# PulverTech_v1.net
KiCad netlist of a schematic drawn in EAGLE
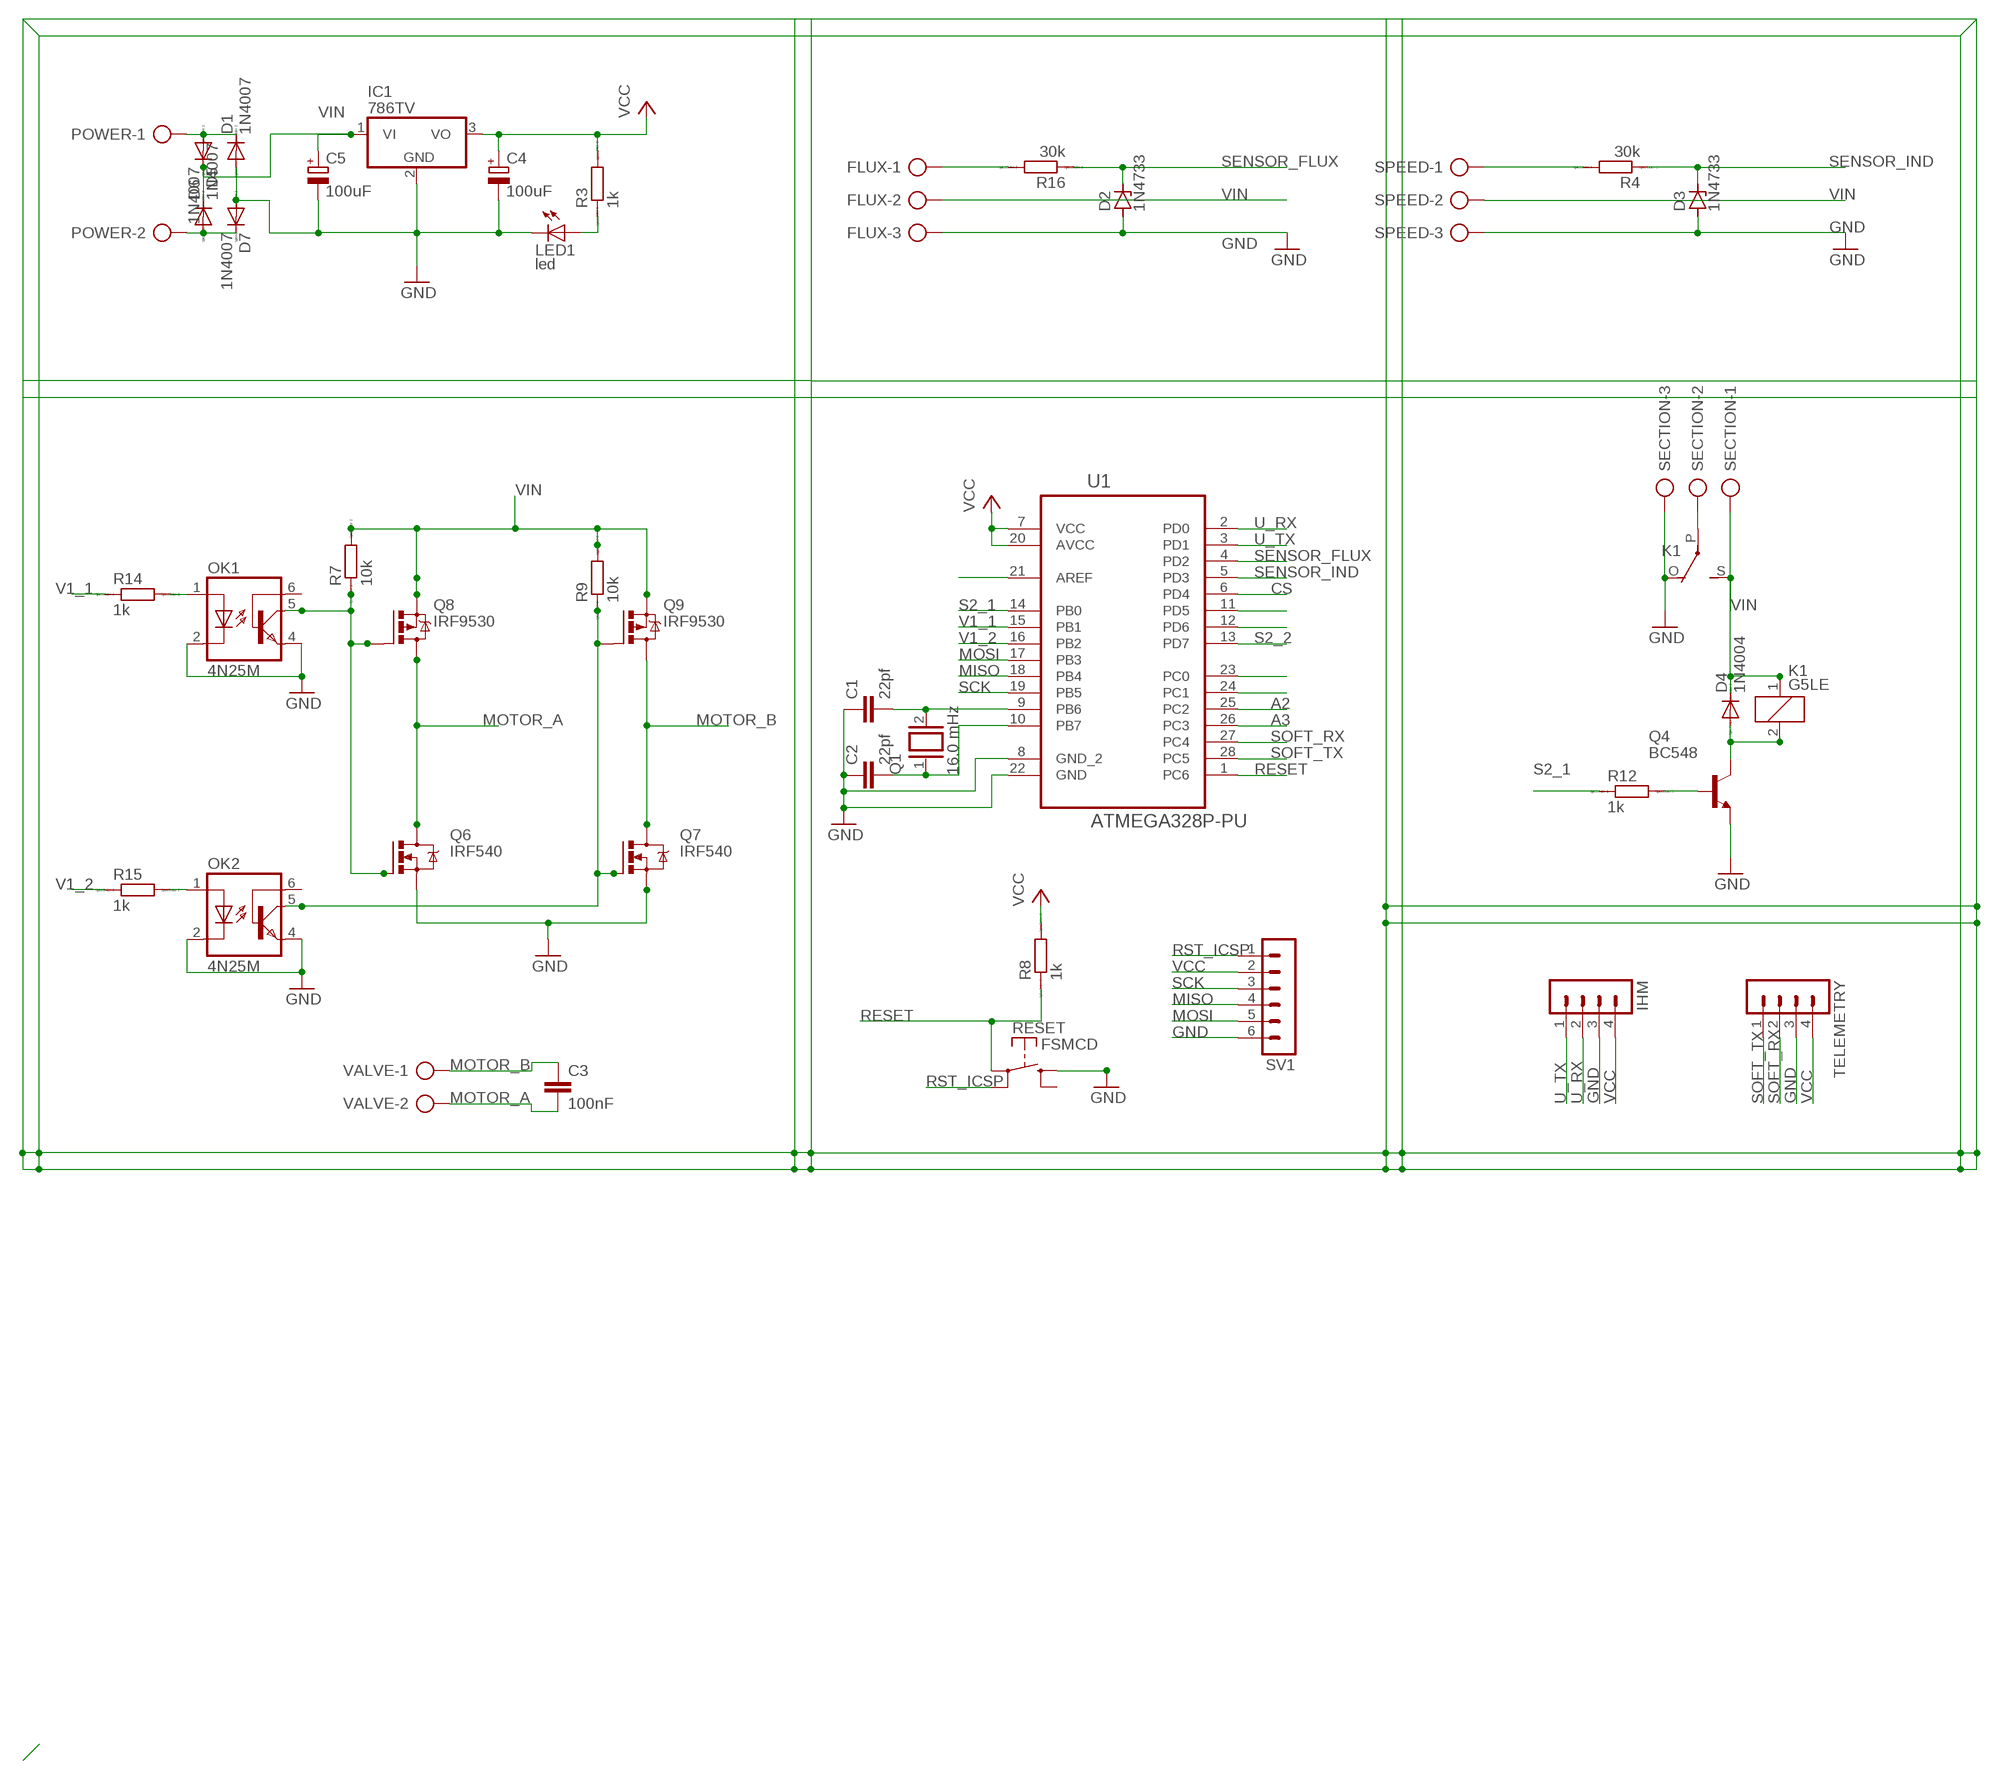
[diagram p0: schematic, sheet 1]

(export (version "E")
  (design (tool "Eeschema 10.0.6"))
  (components
    (comp (ref "C1")
      (value "22pf")
      (footprint "eagle-import:C025-025X050")
      (libsource (lib "eagle-import") (part "C-EU025-025X050"))
    )
    (comp (ref "C2")
      (value "22pf")
      (footprint "eagle-import:C025-025X050")
      (libsource (lib "eagle-import") (part "C-EU025-025X050"))
    )
    (comp (ref "C3")
      (value "100nF")
      (footprint "eagle-import:C2.5-2")
      (libsource (lib "eagle-import") (part "C2.5/2"))
    )
    (comp (ref "C4")
      (value "100uF")
      (footprint "eagle-import:E2,5-5")
      (libsource (lib "eagle-import") (part "CPOL-EUE2.5-5"))
    )
    (comp (ref "C5")
      (value "100uF")
      (footprint "eagle-import:E2,5-5")
      (libsource (lib "eagle-import") (part "CPOL-EUE2.5-5"))
    )
    (comp (ref "D1")
      (value "1N4007")
      (footprint "eagle-import:DO41-10")
      (libsource (lib "eagle-import") (part "1N4004"))
    )
    (comp (ref "D2")
      (value "1N4733")
      (footprint "eagle-import:DO41Z10")
      (libsource (lib "eagle-import") (part "1N4728"))
    )
    (comp (ref "D3")
      (value "1N4733")
      (footprint "eagle-import:DO41Z10")
      (libsource (lib "eagle-import") (part "1N4728"))
    )
    (comp (ref "D4")
      (value "1N4004")
      (footprint "eagle-import:DO41-10")
      (libsource (lib "eagle-import") (part "1N4004"))
    )
    (comp (ref "D5")
      (value "1N4007")
      (footprint "eagle-import:DO41-10")
      (libsource (lib "eagle-import") (part "1N4004"))
    )
    (comp (ref "D6")
      (value "1N4007")
      (footprint "eagle-import:DO41-10")
      (libsource (lib "eagle-import") (part "1N4004"))
    )
    (comp (ref "D7")
      (value "1N4007")
      (footprint "eagle-import:DO41-10")
      (libsource (lib "eagle-import") (part "1N4004"))
    )
    (comp (ref "FLUX")
      (value "AK500/3")
      (footprint "eagle-import:AK500_3")
      (libsource (lib "eagle-import") (part "AK500/3"))
    )
    (comp (ref "IC1")
      (value "786TV")
      (footprint "eagle-import:TO220V")
      (libsource (lib "eagle-import") (part "78TV6"))
    )
    (comp (ref "IHM")
      (value "MA04-1")
      (footprint "eagle-import:MA04-1")
      (libsource (lib "eagle-import") (part "MA04-1"))
    )
    (comp (ref "K1")
      (value "G5LE")
      (footprint "eagle-import:G5LE")
      (libsource (lib "eagle-import") (part "G5LE"))
    )
    (comp (ref "LED1")
      (value "led")
      (footprint "eagle-import:LED3MM")
      (libsource (lib "eagle-import") (part "LED3MM"))
    )
    (comp (ref "OK1")
      (value "4N25M")
      (footprint "eagle-import:DIL06")
      (fields (field (name "MPN") "4N25-M"))
      (libsource (lib "eagle-import") (part "4N?M25"))
    )
    (comp (ref "OK2")
      (value "4N25M")
      (footprint "eagle-import:DIL06")
      (fields (field (name "MPN") "4N25-M"))
      (libsource (lib "eagle-import") (part "4N?M25"))
    )
    (comp (ref "POWER")
      (value "AK500/2")
      (footprint "eagle-import:AK500_2")
      (libsource (lib "eagle-import") (part "AK500/2"))
    )
    (comp (ref "Q1")
      (value "16.0 mHz")
      (footprint "eagle-import:QS")
      (libsource (lib "eagle-import") (part "XTAL/S"))
    )
    (comp (ref "Q4")
      (value "BC548")
      (footprint "eagle-import:TO92-EBC")
      (libsource (lib "eagle-import") (part "BC548"))
    )
    (comp (ref "Q6")
      (value "IRF540")
      (footprint "eagle-import:TO220BV")
      (libsource (lib "eagle-import") (part "IRF540"))
    )
    (comp (ref "Q7")
      (value "IRF540")
      (footprint "eagle-import:TO220BV")
      (libsource (lib "eagle-import") (part "IRF540"))
    )
    (comp (ref "Q8")
      (value "IRF9530")
      (footprint "eagle-import:TO220BV")
      (libsource (lib "eagle-import") (part "IRF9530"))
    )
    (comp (ref "Q9")
      (value "IRF9530")
      (footprint "eagle-import:TO220BV")
      (libsource (lib "eagle-import") (part "IRF9530"))
    )
    (comp (ref "R3")
      (value "1k")
      (footprint "eagle-import:0204_7")
      (libsource (lib "eagle-import") (part "R0204/7"))
    )
    (comp (ref "R4")
      (value "30k")
      (footprint "eagle-import:0204_7")
      (libsource (lib "eagle-import") (part "R0204/7"))
    )
    (comp (ref "R7")
      (value "10k")
      (footprint "eagle-import:0204_7")
      (libsource (lib "eagle-import") (part "R0204/7"))
    )
    (comp (ref "R8")
      (value "1k")
      (footprint "eagle-import:0204_7")
      (libsource (lib "eagle-import") (part "R0204/7"))
    )
    (comp (ref "R9")
      (value "10k")
      (footprint "eagle-import:0204_7")
      (libsource (lib "eagle-import") (part "R0204/7"))
    )
    (comp (ref "R12")
      (value "1k")
      (footprint "eagle-import:0204_7")
      (libsource (lib "eagle-import") (part "R0204/7"))
    )
    (comp (ref "R14")
      (value "1k")
      (footprint "eagle-import:0204_7")
      (libsource (lib "eagle-import") (part "R0204/7"))
    )
    (comp (ref "R15")
      (value "1k")
      (footprint "eagle-import:0204_7")
      (libsource (lib "eagle-import") (part "R0204/7"))
    )
    (comp (ref "R16")
      (value "30k")
      (footprint "eagle-import:0204_7")
      (libsource (lib "eagle-import") (part "R0204/7"))
    )
    (comp (ref "RESET")
      (value "FSMCD")
      (footprint "eagle-import:FSMCD")
      (libsource (lib "eagle-import") (part "FSMCD"))
    )
    (comp (ref "SECTION")
      (value "AK500/3")
      (footprint "eagle-import:AK500_3")
      (libsource (lib "eagle-import") (part "AK500/3"))
    )
    (comp (ref "SPEED")
      (value "AK500/3")
      (footprint "eagle-import:AK500_3")
      (libsource (lib "eagle-import") (part "AK500/3"))
    )
    (comp (ref "SV1")
      (value "MA06-1")
      (footprint "eagle-import:MA06-1")
      (libsource (lib "eagle-import") (part "MA06-1"))
    )
    (comp (ref "TELEMETRY")
      (value "MA04-1")
      (footprint "eagle-import:MA04-1")
      (libsource (lib "eagle-import") (part "MA04-1"))
    )
    (comp (ref "U1")
      (value "ATMEGA328P-PU")
      (footprint "eagle-import:DIP254P762X457-28")
      (libsource (lib "eagle-import") (part "ATMEGA328P-PU"))
    )
    (comp (ref "VALVE")
      (value "AK500/2")
      (footprint "eagle-import:AK500_2")
      (libsource (lib "eagle-import") (part "AK500/2"))
    )
  )
  (nets
    (net (code "1") (name "/A2") (class "Default")
      (node (ref "U1") (pin "25") (pinfunction "PC2_25") (pintype "bidirectional"))
    )
    (net (code "2") (name "/A3") (class "Default")
      (node (ref "U1") (pin "26") (pinfunction "PC3_26") (pintype "bidirectional"))
    )
    (net (code "3") (name "/CS") (class "Default")
      (node (ref "U1") (pin "6") (pinfunction "PD4_6") (pintype "bidirectional"))
    )
    (net (code "4") (name "/MISO") (class "Default")
      (node (ref "SV1") (pin "4") (pinfunction "4_4") (pintype "passive"))
      (node (ref "U1") (pin "18") (pinfunction "PB4_18") (pintype "bidirectional"))
    )
    (net (code "5") (name "/MOSI") (class "Default")
      (node (ref "SV1") (pin "5") (pinfunction "5_5") (pintype "passive"))
      (node (ref "U1") (pin "17") (pinfunction "PB3_17") (pintype "bidirectional"))
    )
    (net (code "6") (name "/MOTOR_A") (class "Default")
      (node (ref "C3") (pin "2") (pinfunction "2_2") (pintype "passive"))
      (node (ref "Q6") (pin "D") (pinfunction "D_D") (pintype "passive"))
      (node (ref "Q8") (pin "D") (pinfunction "D_D") (pintype "passive"))
      (node (ref "VALVE") (pin "2") (pinfunction "KL_2") (pintype "passive"))
    )
    (net (code "7") (name "/MOTOR_B") (class "Default")
      (node (ref "C3") (pin "1") (pinfunction "1_1") (pintype "passive"))
      (node (ref "Q7") (pin "D") (pinfunction "D_D") (pintype "passive"))
      (node (ref "Q9") (pin "D") (pinfunction "D_D") (pintype "passive"))
      (node (ref "VALVE") (pin "1") (pinfunction "KL_1") (pintype "passive"))
    )
    (net (code "8") (name "/RESET") (class "Default")
      (node (ref "R8") (pin "1") (pinfunction "1_1") (pintype "passive"))
      (node (ref "RESET") (pin "P$1") (pinfunction "P_P$1") (pintype "passive"))
      (node (ref "U1") (pin "1") (pinfunction "PC6_1") (pintype "bidirectional"))
    )
    (net (code "9") (name "/RST_ICSP") (class "Default")
      (node (ref "RESET") (pin "P$2") (pinfunction "P_P$2") (pintype "passive"))
      (node (ref "SV1") (pin "1") (pinfunction "1_1") (pintype "passive"))
    )
    (net (code "10") (name "/S2_1") (class "Default")
      (node (ref "R12") (pin "1") (pinfunction "1_1") (pintype "passive"))
      (node (ref "U1") (pin "14") (pinfunction "PB0_14") (pintype "bidirectional"))
    )
    (net (code "11") (name "/S2_2") (class "Default")
      (node (ref "U1") (pin "13") (pinfunction "PD7_13") (pintype "bidirectional"))
    )
    (net (code "12") (name "/SCK") (class "Default")
      (node (ref "SV1") (pin "3") (pinfunction "3_3") (pintype "passive"))
      (node (ref "U1") (pin "19") (pinfunction "PB5_19") (pintype "bidirectional"))
    )
    (net (code "13") (name "/SENSOR_FLUX") (class "Default")
      (node (ref "D2") (pin "C") (pinfunction "C_C") (pintype "passive"))
      (node (ref "R16") (pin "1") (pinfunction "1_1") (pintype "passive"))
      (node (ref "U1") (pin "4") (pinfunction "PD2_4") (pintype "bidirectional"))
    )
    (net (code "14") (name "/SENSOR_IND") (class "Default")
      (node (ref "D3") (pin "C") (pinfunction "C_C") (pintype "passive"))
      (node (ref "R4") (pin "1") (pinfunction "1_1") (pintype "passive"))
      (node (ref "U1") (pin "5") (pinfunction "PD3_5") (pintype "bidirectional"))
    )
    (net (code "15") (name "/SOFT_RX") (class "Default")
      (node (ref "TELEMETRY") (pin "2") (pinfunction "2_2") (pintype "passive"))
      (node (ref "U1") (pin "27") (pinfunction "PC4_27") (pintype "bidirectional"))
    )
    (net (code "16") (name "/SOFT_TX") (class "Default")
      (node (ref "TELEMETRY") (pin "1") (pinfunction "1_1") (pintype "passive"))
      (node (ref "U1") (pin "28") (pinfunction "PC5_28") (pintype "bidirectional"))
    )
    (net (code "17") (name "/U_RX") (class "Default")
      (node (ref "IHM") (pin "2") (pinfunction "2_2") (pintype "passive"))
      (node (ref "U1") (pin "2") (pinfunction "PD0_2") (pintype "bidirectional"))
    )
    (net (code "18") (name "/U_TX") (class "Default")
      (node (ref "IHM") (pin "1") (pinfunction "1_1") (pintype "passive"))
      (node (ref "U1") (pin "3") (pinfunction "PD1_3") (pintype "bidirectional"))
    )
    (net (code "19") (name "/V1_1") (class "Default")
      (node (ref "R14") (pin "1") (pinfunction "1_1") (pintype "passive"))
      (node (ref "U1") (pin "15") (pinfunction "PB1_15") (pintype "bidirectional"))
    )
    (net (code "20") (name "/V1_2") (class "Default")
      (node (ref "R15") (pin "1") (pinfunction "1_1") (pintype "passive"))
      (node (ref "U1") (pin "16") (pinfunction "PB2_16") (pintype "bidirectional"))
    )
    (net (code "21") (name "/VIN") (class "Default")
      (node (ref "C5") (pin "+") (pinfunction "+_+") (pintype "passive"))
      (node (ref "D4") (pin "C") (pinfunction "C_C") (pintype "passive"))
      (node (ref "D5") (pin "C") (pinfunction "C_C") (pintype "passive"))
      (node (ref "D6") (pin "C") (pinfunction "C_C") (pintype "passive"))
      (node (ref "FLUX") (pin "2") (pinfunction "KL_2") (pintype "passive"))
      (node (ref "IC1") (pin "1") (pinfunction "VI_1") (pintype "input"))
      (node (ref "K1") (pin "1") (pinfunction "1_1") (pintype "passive"))
      (node (ref "K1") (pin "S") (pinfunction "S_S") (pintype "passive"))
      (node (ref "Q8") (pin "S") (pinfunction "S_S") (pintype "passive"))
      (node (ref "Q9") (pin "S") (pinfunction "S_S") (pintype "passive"))
      (node (ref "R7") (pin "2") (pinfunction "2_2") (pintype "passive"))
      (node (ref "R9") (pin "2") (pinfunction "2_2") (pintype "passive"))
      (node (ref "SECTION") (pin "1") (pinfunction "KL_1") (pintype "passive"))
      (node (ref "SPEED") (pin "2") (pinfunction "KL_2") (pintype "passive"))
    )
    (net (code "22") (name "GND") (class "Default")
      (node (ref "C1") (pin "1") (pinfunction "1_1") (pintype "passive"))
      (node (ref "C2") (pin "1") (pinfunction "1_1") (pintype "passive"))
      (node (ref "C4") (pin "-") (pinfunction "-_-") (pintype "passive"))
      (node (ref "C5") (pin "-") (pinfunction "-_-") (pintype "passive"))
      (node (ref "D1") (pin "A") (pinfunction "A_A") (pintype "passive"))
      (node (ref "D2") (pin "A") (pinfunction "A_A") (pintype "passive"))
      (node (ref "D3") (pin "A") (pinfunction "A_A") (pintype "passive"))
      (node (ref "D7") (pin "A") (pinfunction "A_A") (pintype "passive"))
      (node (ref "FLUX") (pin "3") (pinfunction "KL_3") (pintype "passive"))
      (node (ref "IC1") (pin "2") (pinfunction "GND_2") (pintype "passive"))
      (node (ref "IHM") (pin "3") (pinfunction "3_3") (pintype "passive"))
      (node (ref "K1") (pin "O") (pinfunction "O_O") (pintype "passive"))
      (node (ref "LED1") (pin "K") (pinfunction "C_K") (pintype "passive"))
      (node (ref "OK1") (pin "2") (pinfunction "C_2") (pintype "passive"))
      (node (ref "OK1") (pin "4") (pinfunction "EMI_4") (pintype "passive"))
      (node (ref "OK2") (pin "2") (pinfunction "C_2") (pintype "passive"))
      (node (ref "OK2") (pin "4") (pinfunction "EMI_4") (pintype "passive"))
      (node (ref "Q4") (pin "E") (pinfunction "E_E") (pintype "passive"))
      (node (ref "Q6") (pin "S") (pinfunction "S_S") (pintype "passive"))
      (node (ref "Q7") (pin "S") (pinfunction "S_S") (pintype "passive"))
      (node (ref "RESET") (pin "P$3") (pinfunction "S_P$3") (pintype "passive"))
      (node (ref "SECTION") (pin "3") (pinfunction "KL_3") (pintype "passive"))
      (node (ref "SPEED") (pin "3") (pinfunction "KL_3") (pintype "passive"))
      (node (ref "SV1") (pin "6") (pinfunction "6_6") (pintype "passive"))
      (node (ref "TELEMETRY") (pin "3") (pinfunction "3_3") (pintype "passive"))
      (node (ref "U1") (pin "22") (pinfunction "GND_22") (pintype "passive"))
      (node (ref "U1") (pin "8") (pinfunction "GND_2_8") (pintype "passive"))
    )
    (net (code "23") (name "Net-(D4-PadA)") (class "Default")
      (node (ref "D4") (pin "A") (pinfunction "A_A") (pintype "passive"))
      (node (ref "K1") (pin "2") (pinfunction "2_2") (pintype "passive"))
      (node (ref "Q4") (pin "C") (pinfunction "C_C") (pintype "passive"))
    )
    (net (code "24") (name "Net-(FLUXA-KL)") (class "Default")
      (node (ref "FLUX") (pin "1") (pinfunction "KL_1") (pintype "passive"))
      (node (ref "R16") (pin "2") (pinfunction "2_2") (pintype "passive"))
    )
    (net (code "25") (name "Net-(LED1-PadA)") (class "Default")
      (node (ref "LED1") (pin "A") (pinfunction "A_A") (pintype "passive"))
      (node (ref "R3") (pin "1") (pinfunction "1_1") (pintype "passive"))
    )
    (net (code "26") (name "Net-(OK1-A)") (class "Default")
      (node (ref "OK1") (pin "1") (pinfunction "A_1") (pintype "passive"))
      (node (ref "R14") (pin "2") (pinfunction "2_2") (pintype "passive"))
    )
    (net (code "27") (name "Net-(OK1-COL)") (class "Default")
      (node (ref "OK1") (pin "5") (pinfunction "COL_5") (pintype "passive"))
      (node (ref "Q6") (pin "G") (pinfunction "G_G") (pintype "passive"))
      (node (ref "Q8") (pin "G") (pinfunction "G_G") (pintype "passive"))
      (node (ref "R7") (pin "1") (pinfunction "1_1") (pintype "passive"))
    )
    (net (code "28") (name "Net-(OK2-A)") (class "Default")
      (node (ref "OK2") (pin "1") (pinfunction "A_1") (pintype "passive"))
      (node (ref "R15") (pin "2") (pinfunction "2_2") (pintype "passive"))
    )
    (net (code "29") (name "Net-(OK2-COL)") (class "Default")
      (node (ref "OK2") (pin "5") (pinfunction "COL_5") (pintype "passive"))
      (node (ref "Q7") (pin "G") (pinfunction "G_G") (pintype "passive"))
      (node (ref "Q9") (pin "G") (pinfunction "G_G") (pintype "passive"))
      (node (ref "R9") (pin "1") (pinfunction "1_1") (pintype "passive"))
    )
    (net (code "30") (name "Net-(POWERA-KL)") (class "Default")
      (node (ref "D1") (pin "C") (pinfunction "C_C") (pintype "passive"))
      (node (ref "D5") (pin "A") (pinfunction "A_A") (pintype "passive"))
      (node (ref "POWER") (pin "1") (pinfunction "KL_1") (pintype "passive"))
    )
    (net (code "31") (name "Net-(POWERB-KL)") (class "Default")
      (node (ref "D6") (pin "A") (pinfunction "A_A") (pintype "passive"))
      (node (ref "D7") (pin "C") (pinfunction "C_C") (pintype "passive"))
      (node (ref "POWER") (pin "2") (pinfunction "KL_2") (pintype "passive"))
    )
    (net (code "32") (name "Net-(Q4-PadB)") (class "Default")
      (node (ref "Q4") (pin "B") (pinfunction "B_B") (pintype "passive"))
      (node (ref "R12") (pin "2") (pinfunction "2_2") (pintype "passive"))
    )
    (net (code "33") (name "Net-(SECTIONB-KL)") (class "Default")
      (node (ref "K1") (pin "P") (pinfunction "P_P") (pintype "passive"))
      (node (ref "SECTION") (pin "2") (pinfunction "KL_2") (pintype "passive"))
    )
    (net (code "34") (name "Net-(SPEEDA-KL)") (class "Default")
      (node (ref "R4") (pin "2") (pinfunction "2_2") (pintype "passive"))
      (node (ref "SPEED") (pin "1") (pinfunction "KL_1") (pintype "passive"))
    )
    (net (code "35") (name "Net-(U1-PB6)") (class "Default")
      (node (ref "C1") (pin "2") (pinfunction "2_2") (pintype "passive"))
      (node (ref "Q1") (pin "2") (pinfunction "2_2") (pintype "passive"))
      (node (ref "U1") (pin "9") (pinfunction "PB6_9") (pintype "bidirectional"))
    )
    (net (code "36") (name "Net-(U1-PB7)") (class "Default")
      (node (ref "C2") (pin "2") (pinfunction "2_2") (pintype "passive"))
      (node (ref "Q1") (pin "1") (pinfunction "1_1") (pintype "passive"))
      (node (ref "U1") (pin "10") (pinfunction "PB7_10") (pintype "bidirectional"))
    )
    (net (code "37") (name "VCC") (class "Default")
      (node (ref "C4") (pin "+") (pinfunction "+_+") (pintype "passive"))
      (node (ref "IC1") (pin "3") (pinfunction "VO_3") (pintype "passive"))
      (node (ref "IHM") (pin "4") (pinfunction "4_4") (pintype "passive"))
      (node (ref "R3") (pin "2") (pinfunction "2_2") (pintype "passive"))
      (node (ref "R8") (pin "2") (pinfunction "2_2") (pintype "passive"))
      (node (ref "SV1") (pin "2") (pinfunction "2_2") (pintype "passive"))
      (node (ref "TELEMETRY") (pin "4") (pinfunction "4_4") (pintype "passive"))
      (node (ref "U1") (pin "20") (pinfunction "AVCC_20") (pintype "power_in"))
      (node (ref "U1") (pin "7") (pinfunction "VCC_7") (pintype "power_in"))
    )
    (net (code "38") (name "unconnected-(OK1-BAS-Pad6)") (class "Default")
      (node (ref "OK1") (pin "6") (pinfunction "BAS_6") (pintype "passive"))
    )
    (net (code "39") (name "unconnected-(OK2-BAS-Pad6)") (class "Default")
      (node (ref "OK2") (pin "6") (pinfunction "BAS_6") (pintype "passive"))
    )
    (net (code "40") (name "unconnected-(RESET-S-PadP$4)") (class "Default")
      (node (ref "RESET") (pin "P$4") (pinfunction "S_P$4") (pintype "passive"))
    )
    (net (code "41") (name "unconnected-(U1-AREF-Pad21)") (class "Default")
      (node (ref "U1") (pin "21") (pinfunction "AREF_21") (pintype "input"))
    )
    (net (code "42") (name "unconnected-(U1-PC0-Pad23)") (class "Default")
      (node (ref "U1") (pin "23") (pinfunction "PC0_23") (pintype "bidirectional"))
    )
    (net (code "43") (name "unconnected-(U1-PC1-Pad24)") (class "Default")
      (node (ref "U1") (pin "24") (pinfunction "PC1_24") (pintype "bidirectional"))
    )
    (net (code "44") (name "unconnected-(U1-PD5-Pad11)") (class "Default")
      (node (ref "U1") (pin "11") (pinfunction "PD5_11") (pintype "bidirectional"))
    )
    (net (code "45") (name "unconnected-(U1-PD6-Pad12)") (class "Default")
      (node (ref "U1") (pin "12") (pinfunction "PD6_12") (pintype "bidirectional"))
    )
  )
)
